# Sheet1.net
KiCad netlist of a schematic drawn in Altium Designer
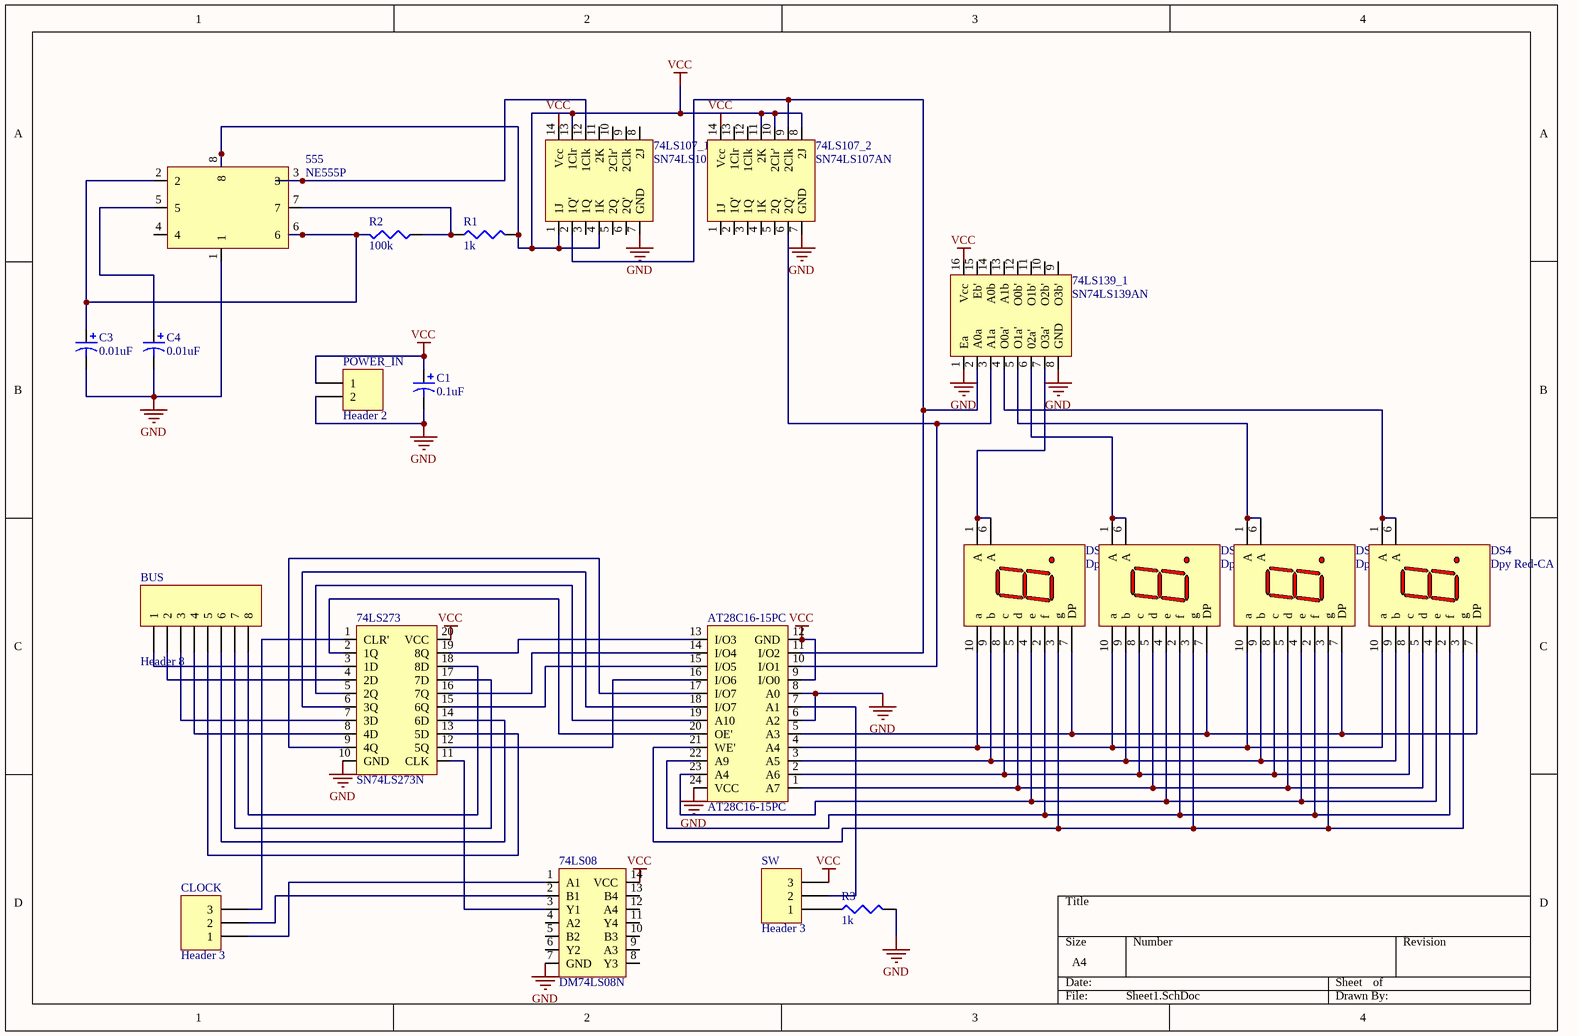
[diagram p0: Sheet1.SchDoc]

(export (version "E")
  (design (tool "Eeschema 10.0.6"))
  (components
    (comp (ref "74LS08")
      (value "DM74LS08N")
      (footprint "SN74LS08N")
      (description "IC GATE AND 4CH 2-INP 14-DIP")
      (fields (field (name "MANUFACTURER") "ON Semiconductor / Fairchild"))
      (libsource (lib "part_library") (part "DM74LS08N"))
    )
    (comp (ref "74LS107_1")
      (value "SN74LS107AN")
      (footprint "DM74LS107")
      (description "Flip Flop JK-Type Neg-Edge 2-Element 14-Pin PDIP Tube")
      (fields (field (name "MANUFACTURER") "Texas Instruments"))
      (libsource (lib "part_library") (part "SN74LS107AN"))
    )
    (comp (ref "74LS107_2")
      (value "SN74LS107AN")
      (footprint "DM74LS107")
      (description "Flip Flop JK-Type Neg-Edge 2-Element 14-Pin PDIP Tube")
      (fields (field (name "MANUFACTURER") "Texas Instruments"))
      (libsource (lib "part_library") (part "SN74LS107AN"))
    )
    (comp (ref "74LS139_1")
      (value "SN74LS139AN")
      (footprint "SN74LS139AN")
      (description "TEXAS INSTRUMENTS         SN74LS139AN            IC, DECODER/DEMUX, 74LS139")
      (fields (field (name "MANUFACTURER") "Texas Instruments"))
      (libsource (lib "part_library") (part "SN74LS139AN"))
    )
    (comp (ref "74LS273")
      (value "SN74LS273N")
      (footprint "SN74LS273N")
      (description "IC D-TYPE POS TRG SNGL 20DIP")
      (fields (field (name "MANUFACTURER") "Texas Instruments"))
      (libsource (lib "part_library") (part "SN74LS273N"))
    )
    (comp (ref "555")
      (value "NE555P")
      (footprint "LM555")
      (description "TEXAS INSTRUMENTS         NE555P            TIMER SINGLE PRECISION,DIP8 ,0.5MHZ")
      (fields (field (name "MANUFACTURER") "Texas Instruments"))
      (libsource (lib "part_library") (part "NE555P"))
    )
    (comp (ref "AT28C16-15PC")
      (value "AT28C16-15PC")
      (footprint "AT28C16-15PC")
      (fields (field (name "MANUFACTURER") "Microchip / Atmel"))
      (libsource (lib "part_library") (part "AT28C16-15PC"))
    )
    (comp (ref "BUS")
      (value "Header 8")
      (footprint "HDR1X8")
      (description "Header, 8-Pin")
      (fields (field (name "PUBLISHER") "Altium Limited"))
      (libsource (lib "Miscellaneous Connectors") (part "Header 8"))
    )
    (comp (ref "C1")
      (value "0.1uF")
      (footprint "C0805")
      (description "Polarized Capacitor (Surface Mount)")
      (fields (field (name "PUBLISHER") "Altium Limited"))
      (libsource (lib "Miscellaneous Devices") (part "Cap Pol3"))
    )
    (comp (ref "C3")
      (value "0.01uF")
      (footprint "C0805")
      (description "Polarized Capacitor (Surface Mount)")
      (fields (field (name "PUBLISHER") "Altium Limited"))
      (libsource (lib "Miscellaneous Devices") (part "Cap Pol3"))
    )
    (comp (ref "C4")
      (value "0.01uF")
      (footprint "C0805")
      (description "Polarized Capacitor (Surface Mount)")
      (fields (field (name "PUBLISHER") "Altium Limited"))
      (libsource (lib "Miscellaneous Devices") (part "Cap Pol3"))
    )
    (comp (ref "CLOCK")
      (value "Header 3")
      (footprint "HDR1X3")
      (description "Header, 3-Pin")
      (fields (field (name "PUBLISHER") "Altium Limited"))
      (libsource (lib "Miscellaneous Connectors") (part "Header 3"))
    )
    (comp (ref "DS1")
      (value "Dpy Red-CA")
      (footprint "7-segment")
      (description "7.62 mm Black Surface HER 7-Segment Display: CA, RH DP")
      (fields (field (name "PUBLISHER") "Altium Limited"))
      (libsource (lib "Miscellaneous Devices") (part "Dpy Red-CA"))
    )
    (comp (ref "DS2")
      (value "Dpy Red-CA")
      (footprint "7-segment")
      (description "7.62 mm Black Surface HER 7-Segment Display: CA, RH DP")
      (fields (field (name "PUBLISHER") "Altium Limited"))
      (libsource (lib "Miscellaneous Devices") (part "Dpy Red-CA"))
    )
    (comp (ref "DS3")
      (value "Dpy Red-CA")
      (footprint "7-segment")
      (description "7.62 mm Black Surface HER 7-Segment Display: CA, RH DP")
      (fields (field (name "PUBLISHER") "Altium Limited"))
      (libsource (lib "Miscellaneous Devices") (part "Dpy Red-CA"))
    )
    (comp (ref "DS4")
      (value "Dpy Red-CA")
      (footprint "7-segment")
      (description "7.62 mm Black Surface HER 7-Segment Display: CA, RH DP")
      (fields (field (name "PUBLISHER") "Altium Limited"))
      (libsource (lib "Miscellaneous Devices") (part "Dpy Red-CA"))
    )
    (comp (ref "POWER_IN")
      (value "Header 2")
      (footprint "HDR1X2")
      (description "Header, 2-Pin")
      (fields (field (name "PUBLISHER") "Altium Limited"))
      (libsource (lib "Miscellaneous Connectors") (part "Header 2"))
    )
    (comp (ref "R1")
      (value "1k")
      (footprint "6-0805_L")
      (description "Resistor")
      (fields (field (name "PUBLISHER") "Altium Limited"))
      (libsource (lib "Miscellaneous Devices") (part "Res3"))
    )
    (comp (ref "R2")
      (value "100k")
      (footprint "6-0805_L")
      (description "Resistor")
      (fields (field (name "PUBLISHER") "Altium Limited"))
      (libsource (lib "Miscellaneous Devices") (part "Res3"))
    )
    (comp (ref "R3")
      (value "1k")
      (footprint "6-0805_L")
      (description "Resistor")
      (fields (field (name "PUBLISHER") "Altium Limited"))
      (libsource (lib "Miscellaneous Devices") (part "Res3"))
    )
    (comp (ref "SW")
      (value "Header 3")
      (footprint "HDR1X3")
      (description "Header, 3-Pin")
      (fields (field (name "PUBLISHER") "Altium Limited"))
      (libsource (lib "Miscellaneous Connectors") (part "Header 3"))
    )
  )
  (nets
    (net (code "1") (name "GND") (class "Default")
      (node (ref "555") (pin "1") (pinfunction "1_1") (pintype "passive"))
      (node (ref "74LS08") (pin "7") (pinfunction "GND_7") (pintype "passive"))
      (node (ref "74LS107_1") (pin "7") (pinfunction "GND_7") (pintype "passive"))
      (node (ref "74LS107_2") (pin "7") (pinfunction "GND_7") (pintype "passive"))
      (node (ref "74LS139_1") (pin "1") (pinfunction "Ea_1") (pintype "passive"))
      (node (ref "74LS139_1") (pin "8") (pinfunction "GND_8") (pintype "passive"))
      (node (ref "74LS273") (pin "10") (pinfunction "GND_10") (pintype "passive"))
      (node (ref "AT28C16-15PC") (pin "24") (pinfunction "VCC_24") (pintype "passive"))
      (node (ref "AT28C16-15PC") (pin "6") (pinfunction "A2_6") (pintype "passive"))
      (node (ref "AT28C16-15PC") (pin "8") (pinfunction "A0_8") (pintype "passive"))
      (node (ref "C1") (pin "2") (pinfunction "2_2") (pintype "passive"))
      (node (ref "C3") (pin "2") (pinfunction "2_2") (pintype "passive"))
      (node (ref "C4") (pin "2") (pinfunction "2_2") (pintype "passive"))
      (node (ref "POWER_IN") (pin "2") (pinfunction "2_2") (pintype "passive"))
      (node (ref "R3") (pin "2") (pinfunction "2_2") (pintype "passive"))
    )
    (net (code "2") (name "Net-(74LS08-A1)") (class "Default")
      (node (ref "74LS08") (pin "1") (pinfunction "A1_1") (pintype "passive"))
      (node (ref "CLOCK") (pin "1") (pinfunction "1_1") (pintype "passive"))
    )
    (net (code "3") (name "Net-(74LS08-B1)") (class "Default")
      (node (ref "74LS08") (pin "2") (pinfunction "B1_2") (pintype "passive"))
      (node (ref "CLOCK") (pin "2") (pinfunction "2_2") (pintype "passive"))
    )
    (net (code "4") (name "Net-(74LS08-Y1)") (class "Default")
      (node (ref "74LS08") (pin "3") (pinfunction "Y1_3") (pintype "passive"))
      (node (ref "74LS273") (pin "11") (pinfunction "CLK_11") (pintype "passive"))
    )
    (net (code "5") (name "Net-(74LS107_1-1Clk)") (class "Default")
      (node (ref "555") (pin "3") (pinfunction "3_3") (pintype "passive"))
      (node (ref "74LS107_1") (pin "12") (pinfunction "1Clk_12") (pintype "passive"))
    )
    (net (code "6") (name "Net-(74LS107_1-1Q')") (class "Default")
      (node (ref "74LS107_1") (pin "2") (pinfunction "1Q'_2") (pintype "passive"))
      (node (ref "74LS107_2") (pin "9") (pinfunction "2Clk_9") (pintype "passive"))
      (node (ref "74LS139_1") (pin "2") (pinfunction "A0a_2") (pintype "passive"))
      (node (ref "AT28C16-15PC") (pin "11") (pinfunction "I/O2_11") (pintype "passive"))
    )
    (net (code "7") (name "Net-(74LS107_2-2Q')") (class "Default")
      (node (ref "74LS107_2") (pin "6") (pinfunction "2Q'_6") (pintype "passive"))
      (node (ref "74LS139_1") (pin "3") (pinfunction "A1a_3") (pintype "passive"))
      (node (ref "AT28C16-15PC") (pin "10") (pinfunction "I/O1_10") (pintype "passive"))
    )
    (net (code "8") (name "Net-(74LS139_1-02a')") (class "Default")
      (node (ref "74LS139_1") (pin "6") (pinfunction "02a'_6") (pintype "passive"))
      (node (ref "DS2") (pin "1") (pinfunction "A_1") (pintype "passive"))
      (node (ref "DS2") (pin "6") (pinfunction "A_6") (pintype "passive"))
    )
    (net (code "9") (name "Net-(74LS139_1-O0a')") (class "Default")
      (node (ref "74LS139_1") (pin "4") (pinfunction "O0a'_4") (pintype "passive"))
      (node (ref "DS4") (pin "1") (pinfunction "A_1") (pintype "passive"))
      (node (ref "DS4") (pin "6") (pinfunction "A_6") (pintype "passive"))
    )
    (net (code "10") (name "Net-(74LS139_1-O1a')") (class "Default")
      (node (ref "74LS139_1") (pin "5") (pinfunction "O1a'_5") (pintype "passive"))
      (node (ref "DS3") (pin "1") (pinfunction "A_1") (pintype "passive"))
      (node (ref "DS3") (pin "6") (pinfunction "A_6") (pintype "passive"))
    )
    (net (code "11") (name "Net-(74LS139_1-O3a')") (class "Default")
      (node (ref "74LS139_1") (pin "7") (pinfunction "O3a'_7") (pintype "passive"))
      (node (ref "DS1") (pin "1") (pinfunction "A_1") (pintype "passive"))
      (node (ref "DS1") (pin "6") (pinfunction "A_6") (pintype "passive"))
    )
    (net (code "12") (name "Net-(74LS273-1D)") (class "Default")
      (node (ref "74LS273") (pin "3") (pinfunction "1D_3") (pintype "passive"))
      (node (ref "BUS") (pin "1") (pinfunction "1_1") (pintype "passive"))
    )
    (net (code "13") (name "Net-(74LS273-1Q)") (class "Default")
      (node (ref "74LS273") (pin "2") (pinfunction "1Q_2") (pintype "passive"))
      (node (ref "AT28C16-15PC") (pin "20") (pinfunction "OE'_20") (pintype "passive"))
    )
    (net (code "14") (name "Net-(74LS273-2D)") (class "Default")
      (node (ref "74LS273") (pin "4") (pinfunction "2D_4") (pintype "passive"))
      (node (ref "BUS") (pin "2") (pinfunction "2_2") (pintype "passive"))
    )
    (net (code "15") (name "Net-(74LS273-2Q)") (class "Default")
      (node (ref "74LS273") (pin "5") (pinfunction "2Q_5") (pintype "passive"))
      (node (ref "AT28C16-15PC") (pin "19") (pinfunction "A10_19") (pintype "passive"))
    )
    (net (code "16") (name "Net-(74LS273-3D)") (class "Default")
      (node (ref "74LS273") (pin "7") (pinfunction "3D_7") (pintype "passive"))
      (node (ref "BUS") (pin "3") (pinfunction "3_3") (pintype "passive"))
    )
    (net (code "17") (name "Net-(74LS273-3Q)") (class "Default")
      (node (ref "74LS273") (pin "6") (pinfunction "3Q_6") (pintype "passive"))
      (node (ref "AT28C16-15PC") (pin "18") (pinfunction "I/O7_18") (pintype "passive"))
    )
    (net (code "18") (name "Net-(74LS273-4D)") (class "Default")
      (node (ref "74LS273") (pin "8") (pinfunction "4D_8") (pintype "passive"))
      (node (ref "BUS") (pin "4") (pinfunction "4_4") (pintype "passive"))
    )
    (net (code "19") (name "Net-(74LS273-4Q)") (class "Default")
      (node (ref "74LS273") (pin "9") (pinfunction "4Q_9") (pintype "passive"))
      (node (ref "AT28C16-15PC") (pin "17") (pinfunction "I/O7_17") (pintype "passive"))
    )
    (net (code "20") (name "Net-(74LS273-5D)") (class "Default")
      (node (ref "74LS273") (pin "13") (pinfunction "5D_13") (pintype "passive"))
      (node (ref "BUS") (pin "5") (pinfunction "5_5") (pintype "passive"))
    )
    (net (code "21") (name "Net-(74LS273-5Q)") (class "Default")
      (node (ref "74LS273") (pin "12") (pinfunction "5Q_12") (pintype "passive"))
      (node (ref "AT28C16-15PC") (pin "16") (pinfunction "I/O6_16") (pintype "passive"))
    )
    (net (code "22") (name "Net-(74LS273-6D)") (class "Default")
      (node (ref "74LS273") (pin "14") (pinfunction "6D_14") (pintype "passive"))
      (node (ref "BUS") (pin "6") (pinfunction "6_6") (pintype "passive"))
    )
    (net (code "23") (name "Net-(74LS273-6Q)") (class "Default")
      (node (ref "74LS273") (pin "15") (pinfunction "6Q_15") (pintype "passive"))
      (node (ref "AT28C16-15PC") (pin "15") (pinfunction "I/O5_15") (pintype "passive"))
    )
    (net (code "24") (name "Net-(74LS273-7D)") (class "Default")
      (node (ref "74LS273") (pin "17") (pinfunction "7D_17") (pintype "passive"))
      (node (ref "BUS") (pin "7") (pinfunction "7_7") (pintype "passive"))
    )
    (net (code "25") (name "Net-(74LS273-7Q)") (class "Default")
      (node (ref "74LS273") (pin "16") (pinfunction "7Q_16") (pintype "passive"))
      (node (ref "AT28C16-15PC") (pin "14") (pinfunction "I/O4_14") (pintype "passive"))
    )
    (net (code "26") (name "Net-(74LS273-8D)") (class "Default")
      (node (ref "74LS273") (pin "18") (pinfunction "8D_18") (pintype "passive"))
      (node (ref "BUS") (pin "8") (pinfunction "8_8") (pintype "passive"))
    )
    (net (code "27") (name "Net-(74LS273-8Q)") (class "Default")
      (node (ref "74LS273") (pin "19") (pinfunction "8Q_19") (pintype "passive"))
      (node (ref "AT28C16-15PC") (pin "13") (pinfunction "I/O3_13") (pintype "passive"))
    )
    (net (code "28") (name "Net-(74LS273-CLR')") (class "Default")
      (node (ref "74LS273") (pin "1") (pinfunction "CLR'_1") (pintype "passive"))
      (node (ref "CLOCK") (pin "3") (pinfunction "3_3") (pintype "passive"))
    )
    (net (code "29") (name "Net-(555-Pad2)") (class "Default")
      (node (ref "555") (pin "2") (pinfunction "2_2") (pintype "passive"))
      (node (ref "555") (pin "6") (pinfunction "6_6") (pintype "passive"))
      (node (ref "C3") (pin "1") (pinfunction "1_1") (pintype "passive"))
      (node (ref "R2") (pin "2") (pinfunction "2_2") (pintype "passive"))
    )
    (net (code "30") (name "Net-(555-Pad5)") (class "Default")
      (node (ref "555") (pin "5") (pinfunction "5_5") (pintype "passive"))
      (node (ref "C4") (pin "1") (pinfunction "1_1") (pintype "passive"))
    )
    (net (code "31") (name "Net-(555-Pad7)") (class "Default")
      (node (ref "555") (pin "7") (pinfunction "7_7") (pintype "passive"))
      (node (ref "R1") (pin "1") (pinfunction "1_1") (pintype "passive"))
      (node (ref "R2") (pin "1") (pinfunction "1_1") (pintype "passive"))
    )
    (net (code "32") (name "Net-(AT28C16-15PC-A1)") (class "Default")
      (node (ref "AT28C16-15PC") (pin "7") (pinfunction "A1_7") (pintype "passive"))
      (node (ref "SW") (pin "2") (pinfunction "2_2") (pintype "passive"))
    )
    (net (code "33") (name "Net-(AT28C16-15PC-A3)") (class "Default")
      (node (ref "AT28C16-15PC") (pin "5") (pinfunction "A3_5") (pintype "passive"))
      (node (ref "DS1") (pin "7") (pinfunction "DP_7") (pintype "passive"))
      (node (ref "DS2") (pin "7") (pinfunction "DP_7") (pintype "passive"))
      (node (ref "DS3") (pin "7") (pinfunction "DP_7") (pintype "passive"))
      (node (ref "DS4") (pin "7") (pinfunction "DP_7") (pintype "passive"))
    )
    (net (code "34") (name "Net-(AT28C16-15PC-A5)") (class "Default")
      (node (ref "AT28C16-15PC") (pin "3") (pinfunction "A5_3") (pintype "passive"))
      (node (ref "DS1") (pin "9") (pinfunction "b_9") (pintype "passive"))
      (node (ref "DS2") (pin "9") (pinfunction "b_9") (pintype "passive"))
      (node (ref "DS3") (pin "9") (pinfunction "b_9") (pintype "passive"))
      (node (ref "DS4") (pin "9") (pinfunction "b_9") (pintype "passive"))
    )
    (net (code "35") (name "Net-(AT28C16-15PC-A6)") (class "Default")
      (node (ref "AT28C16-15PC") (pin "2") (pinfunction "A6_2") (pintype "passive"))
      (node (ref "DS1") (pin "8") (pinfunction "c_8") (pintype "passive"))
      (node (ref "DS2") (pin "8") (pinfunction "c_8") (pintype "passive"))
      (node (ref "DS3") (pin "8") (pinfunction "c_8") (pintype "passive"))
      (node (ref "DS4") (pin "8") (pinfunction "c_8") (pintype "passive"))
    )
    (net (code "36") (name "Net-(AT28C16-15PC-A7)") (class "Default")
      (node (ref "AT28C16-15PC") (pin "1") (pinfunction "A7_1") (pintype "passive"))
      (node (ref "DS1") (pin "5") (pinfunction "d_5") (pintype "passive"))
      (node (ref "DS2") (pin "5") (pinfunction "d_5") (pintype "passive"))
      (node (ref "DS3") (pin "5") (pinfunction "d_5") (pintype "passive"))
      (node (ref "DS4") (pin "5") (pinfunction "d_5") (pintype "passive"))
    )
    (net (code "37") (name "Net-(AT28C16-15PC-A9)") (class "Default")
      (node (ref "AT28C16-15PC") (pin "22") (pinfunction "A9_22") (pintype "passive"))
      (node (ref "DS1") (pin "2") (pinfunction "f_2") (pintype "passive"))
      (node (ref "DS2") (pin "2") (pinfunction "f_2") (pintype "passive"))
      (node (ref "DS3") (pin "2") (pinfunction "f_2") (pintype "passive"))
      (node (ref "DS4") (pin "2") (pinfunction "f_2") (pintype "passive"))
    )
    (net (code "38") (name "Net-(AT28C16-15PC-WE')") (class "Default")
      (node (ref "AT28C16-15PC") (pin "21") (pinfunction "WE'_21") (pintype "passive"))
      (node (ref "DS1") (pin "3") (pinfunction "g_3") (pintype "passive"))
      (node (ref "DS2") (pin "3") (pinfunction "g_3") (pintype "passive"))
      (node (ref "DS3") (pin "3") (pinfunction "g_3") (pintype "passive"))
      (node (ref "DS4") (pin "3") (pinfunction "g_3") (pintype "passive"))
    )
    (net (code "39") (name "Net-(DS1-a)") (class "Default")
      (node (ref "AT28C16-15PC") (pin "4") (pinfunction "A4_4") (pintype "passive"))
      (node (ref "DS1") (pin "10") (pinfunction "a_10") (pintype "passive"))
      (node (ref "DS2") (pin "10") (pinfunction "a_10") (pintype "passive"))
      (node (ref "DS3") (pin "10") (pinfunction "a_10") (pintype "passive"))
      (node (ref "DS4") (pin "10") (pinfunction "a_10") (pintype "passive"))
    )
    (net (code "40") (name "Net-(DS1-e)") (class "Default")
      (node (ref "AT28C16-15PC") (pin "23") (pinfunction "A4_23") (pintype "passive"))
      (node (ref "DS1") (pin "4") (pinfunction "e_4") (pintype "passive"))
      (node (ref "DS2") (pin "4") (pinfunction "e_4") (pintype "passive"))
      (node (ref "DS3") (pin "4") (pinfunction "e_4") (pintype "passive"))
      (node (ref "DS4") (pin "4") (pinfunction "e_4") (pintype "passive"))
    )
    (net (code "41") (name "Net-(R3-Pad1)") (class "Default")
      (node (ref "R3") (pin "1") (pinfunction "1_1") (pintype "passive"))
      (node (ref "SW") (pin "1") (pinfunction "1_1") (pintype "passive"))
    )
    (net (code "42") (name "VCC") (class "Default")
      (node (ref "555") (pin "8") (pinfunction "8_8") (pintype "passive"))
      (node (ref "74LS08") (pin "14") (pinfunction "VCC_14") (pintype "passive"))
      (node (ref "74LS107_1") (pin "1") (pinfunction "1J_1") (pintype "passive"))
      (node (ref "74LS107_1") (pin "13") (pinfunction "1Clr_13") (pintype "passive"))
      (node (ref "74LS107_1") (pin "14") (pinfunction "Vcc_14") (pintype "passive"))
      (node (ref "74LS107_1") (pin "4") (pinfunction "1K_4") (pintype "passive"))
      (node (ref "74LS107_2") (pin "10") (pinfunction "2Clr'_10") (pintype "passive"))
      (node (ref "74LS107_2") (pin "11") (pinfunction "2K_11") (pintype "passive"))
      (node (ref "74LS107_2") (pin "14") (pinfunction "Vcc_14") (pintype "passive"))
      (node (ref "74LS107_2") (pin "8") (pinfunction "2J_8") (pintype "passive"))
      (node (ref "74LS139_1") (pin "16") (pinfunction "Vcc_16") (pintype "passive"))
      (node (ref "74LS273") (pin "20") (pinfunction "VCC_20") (pintype "passive"))
      (node (ref "AT28C16-15PC") (pin "12") (pinfunction "GND_12") (pintype "passive"))
      (node (ref "AT28C16-15PC") (pin "9") (pinfunction "I/O0_9") (pintype "passive"))
      (node (ref "C1") (pin "1") (pinfunction "1_1") (pintype "passive"))
      (node (ref "POWER_IN") (pin "1") (pinfunction "1_1") (pintype "passive"))
      (node (ref "R1") (pin "2") (pinfunction "2_2") (pintype "passive"))
      (node (ref "SW") (pin "3") (pinfunction "3_3") (pintype "passive"))
    )
    (net (code "43") (name "unconnected-(74LS08-A2-Pad4)") (class "Default")
      (node (ref "74LS08") (pin "4") (pinfunction "A2_4") (pintype "passive"))
    )
    (net (code "44") (name "unconnected-(74LS08-A3-Pad9)") (class "Default")
      (node (ref "74LS08") (pin "9") (pinfunction "A3_9") (pintype "passive"))
    )
    (net (code "45") (name "unconnected-(74LS08-A4-Pad12)") (class "Default")
      (node (ref "74LS08") (pin "12") (pinfunction "A4_12") (pintype "passive"))
    )
    (net (code "46") (name "unconnected-(74LS08-B2-Pad5)") (class "Default")
      (node (ref "74LS08") (pin "5") (pinfunction "B2_5") (pintype "passive"))
    )
    (net (code "47") (name "unconnected-(74LS08-B3-Pad10)") (class "Default")
      (node (ref "74LS08") (pin "10") (pinfunction "B3_10") (pintype "passive"))
    )
    (net (code "48") (name "unconnected-(74LS08-B4-Pad13)") (class "Default")
      (node (ref "74LS08") (pin "13") (pinfunction "B4_13") (pintype "passive"))
    )
    (net (code "49") (name "unconnected-(74LS08-Y2-Pad6)") (class "Default")
      (node (ref "74LS08") (pin "6") (pinfunction "Y2_6") (pintype "passive"))
    )
    (net (code "50") (name "unconnected-(74LS08-Y3-Pad8)") (class "Default")
      (node (ref "74LS08") (pin "8") (pinfunction "Y3_8") (pintype "passive"))
    )
    (net (code "51") (name "unconnected-(74LS08-Y4-Pad11)") (class "Default")
      (node (ref "74LS08") (pin "11") (pinfunction "Y4_11") (pintype "passive"))
    )
    (net (code "52") (name "unconnected-(74LS107_1-1Q-Pad3)") (class "Default")
      (node (ref "74LS107_1") (pin "3") (pinfunction "1Q_3") (pintype "passive"))
    )
    (net (code "53") (name "unconnected-(74LS107_1-2Clk-Pad9)") (class "Default")
      (node (ref "74LS107_1") (pin "9") (pinfunction "2Clk_9") (pintype "passive"))
    )
    (net (code "54") (name "unconnected-(74LS107_1-2Clr'-Pad10)") (class "Default")
      (node (ref "74LS107_1") (pin "10") (pinfunction "2Clr'_10") (pintype "passive"))
    )
    (net (code "55") (name "unconnected-(74LS107_1-2J-Pad8)") (class "Default")
      (node (ref "74LS107_1") (pin "8") (pinfunction "2J_8") (pintype "passive"))
    )
    (net (code "56") (name "unconnected-(74LS107_1-2K-Pad11)") (class "Default")
      (node (ref "74LS107_1") (pin "11") (pinfunction "2K_11") (pintype "passive"))
    )
    (net (code "57") (name "unconnected-(74LS107_1-2Q'-Pad6)") (class "Default")
      (node (ref "74LS107_1") (pin "6") (pinfunction "2Q'_6") (pintype "passive"))
    )
    (net (code "58") (name "unconnected-(74LS107_1-2Q-Pad5)") (class "Default")
      (node (ref "74LS107_1") (pin "5") (pinfunction "2Q_5") (pintype "passive"))
    )
    (net (code "59") (name "unconnected-(74LS107_2-1Clk-Pad12)") (class "Default")
      (node (ref "74LS107_2") (pin "12") (pinfunction "1Clk_12") (pintype "passive"))
    )
    (net (code "60") (name "unconnected-(74LS107_2-1Clr-Pad13)") (class "Default")
      (node (ref "74LS107_2") (pin "13") (pinfunction "1Clr_13") (pintype "passive"))
    )
    (net (code "61") (name "unconnected-(74LS107_2-1J-Pad1)") (class "Default")
      (node (ref "74LS107_2") (pin "1") (pinfunction "1J_1") (pintype "passive"))
    )
    (net (code "62") (name "unconnected-(74LS107_2-1K-Pad4)") (class "Default")
      (node (ref "74LS107_2") (pin "4") (pinfunction "1K_4") (pintype "passive"))
    )
    (net (code "63") (name "unconnected-(74LS107_2-1Q'-Pad2)") (class "Default")
      (node (ref "74LS107_2") (pin "2") (pinfunction "1Q'_2") (pintype "passive"))
    )
    (net (code "64") (name "unconnected-(74LS107_2-1Q-Pad3)") (class "Default")
      (node (ref "74LS107_2") (pin "3") (pinfunction "1Q_3") (pintype "passive"))
    )
    (net (code "65") (name "unconnected-(74LS107_2-2Q-Pad5)") (class "Default")
      (node (ref "74LS107_2") (pin "5") (pinfunction "2Q_5") (pintype "passive"))
    )
    (net (code "66") (name "unconnected-(74LS139_1-A0b-Pad14)") (class "Default")
      (node (ref "74LS139_1") (pin "14") (pinfunction "A0b_14") (pintype "passive"))
    )
    (net (code "67") (name "unconnected-(74LS139_1-A1b-Pad13)") (class "Default")
      (node (ref "74LS139_1") (pin "13") (pinfunction "A1b_13") (pintype "passive"))
    )
    (net (code "68") (name "unconnected-(74LS139_1-Eb'-Pad15)") (class "Default")
      (node (ref "74LS139_1") (pin "15") (pinfunction "Eb'_15") (pintype "passive"))
    )
    (net (code "69") (name "unconnected-(74LS139_1-O0b'-Pad12)") (class "Default")
      (node (ref "74LS139_1") (pin "12") (pinfunction "O0b'_12") (pintype "passive"))
    )
    (net (code "70") (name "unconnected-(74LS139_1-O1b'-Pad11)") (class "Default")
      (node (ref "74LS139_1") (pin "11") (pinfunction "O1b'_11") (pintype "passive"))
    )
    (net (code "71") (name "unconnected-(74LS139_1-O2b'-Pad10)") (class "Default")
      (node (ref "74LS139_1") (pin "10") (pinfunction "O2b'_10") (pintype "passive"))
    )
    (net (code "72") (name "unconnected-(74LS139_1-O3b'-Pad9)") (class "Default")
      (node (ref "74LS139_1") (pin "9") (pinfunction "O3b'_9") (pintype "passive"))
    )
    (net (code "73") (name "unconnected-(555-Pad4)") (class "Default")
      (node (ref "555") (pin "4") (pinfunction "4_4") (pintype "passive"))
    )
  )
)
